# Mainboard_Debug_Interface.net
KiCad netlist of a schematic drawn in Altium Designer
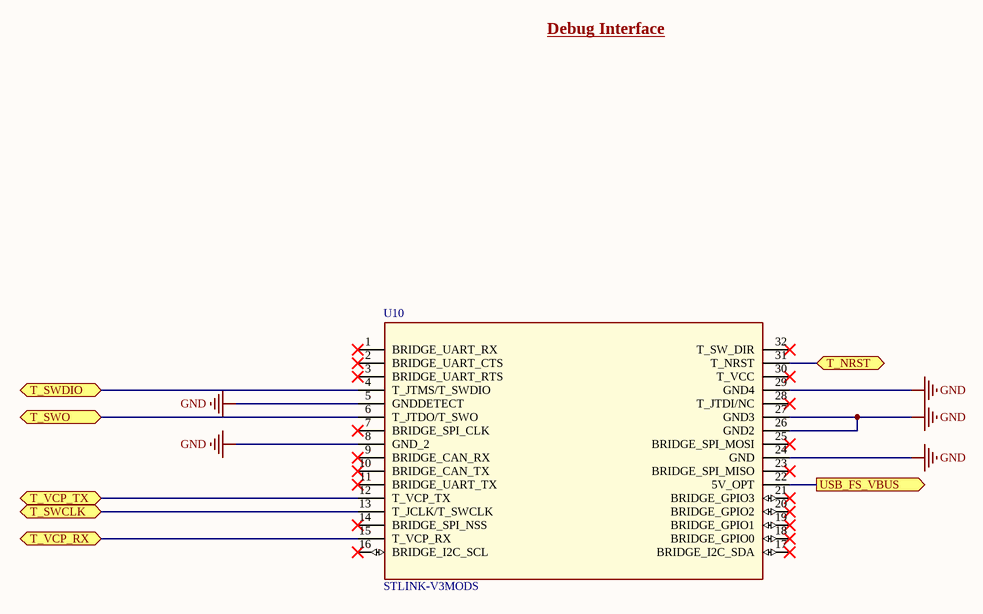
[diagram p0: Mainboard_Debug_Interface.SchDoc]

(export (version "E")
  (design (tool "Eeschema 10.0.6"))
  (components
    (comp (ref "U10")
      (value "STLINK-V3MODS")
      (footprint "STLINK-V3MODS")
      (description "STM32 - Debugger, Programmer (In-Circuit/In-System)")
      (fields (field (name "MF") "STMicroelectronics"))
      (libsource (lib "AltiumLibraries") (part "STLINK-V3MODS"))
    )
  )
  (nets
    (net (code "1") (name "/T_NRST") (class "Default")
      (node (ref "U10") (pin "31") (pinfunction "T_NRST_31") (pintype "passive"))
    )
    (net (code "2") (name "/T_SWCLK") (class "Default")
      (node (ref "U10") (pin "13") (pinfunction "T_JCLK/T_SWCLK_13") (pintype "passive"))
    )
    (net (code "3") (name "/T_SWDIO") (class "Default")
      (node (ref "U10") (pin "4") (pinfunction "T_JTMS/T_SWDIO_4") (pintype "passive"))
    )
    (net (code "4") (name "/T_SWO") (class "Default")
      (node (ref "U10") (pin "6") (pinfunction "T_JTDO/T_SWO_6") (pintype "passive"))
    )
    (net (code "5") (name "/T_VCP_RX") (class "Default")
      (node (ref "U10") (pin "15") (pinfunction "T_VCP_RX_15") (pintype "passive"))
    )
    (net (code "6") (name "/T_VCP_TX") (class "Default")
      (node (ref "U10") (pin "12") (pinfunction "T_VCP_TX_12") (pintype "passive"))
    )
    (net (code "7") (name "/USB_FS_VBUS") (class "Default")
      (node (ref "U10") (pin "22") (pinfunction "5V_OPT_22") (pintype "passive"))
    )
    (net (code "8") (name "GND") (class "Default")
      (node (ref "U10") (pin "24") (pinfunction "GND_24") (pintype "passive"))
      (node (ref "U10") (pin "26") (pinfunction "GND2_26") (pintype "passive"))
      (node (ref "U10") (pin "27") (pinfunction "GND3_27") (pintype "passive"))
      (node (ref "U10") (pin "29") (pinfunction "GND4_29") (pintype "passive"))
      (node (ref "U10") (pin "5") (pinfunction "GNDDETECT_5") (pintype "passive"))
      (node (ref "U10") (pin "8") (pinfunction "GND_2_8") (pintype "passive"))
    )
    (net (code "9") (name "unconnected-(U10-BRIDGE_CAN_RX-Pad9)") (class "Default")
      (node (ref "U10") (pin "9") (pinfunction "BRIDGE_CAN_RX_9") (pintype "passive+no_connect"))
    )
    (net (code "10") (name "unconnected-(U10-BRIDGE_CAN_TX-Pad10)") (class "Default")
      (node (ref "U10") (pin "10") (pinfunction "BRIDGE_CAN_TX_10") (pintype "passive+no_connect"))
    )
    (net (code "11") (name "unconnected-(U10-BRIDGE_GPIO0-Pad18)") (class "Default")
      (node (ref "U10") (pin "18") (pinfunction "BRIDGE_GPIO0_18") (pintype "bidirectional+no_connect"))
    )
    (net (code "12") (name "unconnected-(U10-BRIDGE_GPIO1-Pad19)") (class "Default")
      (node (ref "U10") (pin "19") (pinfunction "BRIDGE_GPIO1_19") (pintype "bidirectional+no_connect"))
    )
    (net (code "13") (name "unconnected-(U10-BRIDGE_GPIO2-Pad20)") (class "Default")
      (node (ref "U10") (pin "20") (pinfunction "BRIDGE_GPIO2_20") (pintype "bidirectional+no_connect"))
    )
    (net (code "14") (name "unconnected-(U10-BRIDGE_GPIO3-Pad21)") (class "Default")
      (node (ref "U10") (pin "21") (pinfunction "BRIDGE_GPIO3_21") (pintype "bidirectional+no_connect"))
    )
    (net (code "15") (name "unconnected-(U10-BRIDGE_I2C_SCL-Pad16)") (class "Default")
      (node (ref "U10") (pin "16") (pinfunction "BRIDGE_I2C_SCL_16") (pintype "bidirectional+no_connect"))
    )
    (net (code "16") (name "unconnected-(U10-BRIDGE_I2C_SDA-Pad17)") (class "Default")
      (node (ref "U10") (pin "17") (pinfunction "BRIDGE_I2C_SDA_17") (pintype "bidirectional+no_connect"))
    )
    (net (code "17") (name "unconnected-(U10-BRIDGE_SPI_CLK-Pad7)") (class "Default")
      (node (ref "U10") (pin "7") (pinfunction "BRIDGE_SPI_CLK_7") (pintype "passive+no_connect"))
    )
    (net (code "18") (name "unconnected-(U10-BRIDGE_SPI_MISO-Pad23)") (class "Default")
      (node (ref "U10") (pin "23") (pinfunction "BRIDGE_SPI_MISO_23") (pintype "passive+no_connect"))
    )
    (net (code "19") (name "unconnected-(U10-BRIDGE_SPI_MOSI-Pad25)") (class "Default")
      (node (ref "U10") (pin "25") (pinfunction "BRIDGE_SPI_MOSI_25") (pintype "passive+no_connect"))
    )
    (net (code "20") (name "unconnected-(U10-BRIDGE_SPI_NSS-Pad14)") (class "Default")
      (node (ref "U10") (pin "14") (pinfunction "BRIDGE_SPI_NSS_14") (pintype "passive+no_connect"))
    )
    (net (code "21") (name "unconnected-(U10-BRIDGE_UART_CTS-Pad2)") (class "Default")
      (node (ref "U10") (pin "2") (pinfunction "BRIDGE_UART_CTS_2") (pintype "passive+no_connect"))
    )
    (net (code "22") (name "unconnected-(U10-BRIDGE_UART_RTS-Pad3)") (class "Default")
      (node (ref "U10") (pin "3") (pinfunction "BRIDGE_UART_RTS_3") (pintype "passive+no_connect"))
    )
    (net (code "23") (name "unconnected-(U10-BRIDGE_UART_RX-Pad1)") (class "Default")
      (node (ref "U10") (pin "1") (pinfunction "BRIDGE_UART_RX_1") (pintype "passive+no_connect"))
    )
    (net (code "24") (name "unconnected-(U10-BRIDGE_UART_TX-Pad11)") (class "Default")
      (node (ref "U10") (pin "11") (pinfunction "BRIDGE_UART_TX_11") (pintype "passive+no_connect"))
    )
    (net (code "25") (name "unconnected-(U10-T_JTDI{slash}NC-Pad28)") (class "Default")
      (node (ref "U10") (pin "28") (pinfunction "T_JTDI/NC_28") (pintype "passive+no_connect"))
    )
    (net (code "26") (name "unconnected-(U10-T_SW_DIR-Pad32)") (class "Default")
      (node (ref "U10") (pin "32") (pinfunction "T_SW_DIR_32") (pintype "passive+no_connect"))
    )
    (net (code "27") (name "unconnected-(U10-T_VCC-Pad30)") (class "Default")
      (node (ref "U10") (pin "30") (pinfunction "T_VCC_30") (pintype "passive+no_connect"))
    )
  )
)
